# sound-detector.net
KiCad netlist of a schematic drawn in EAGLE
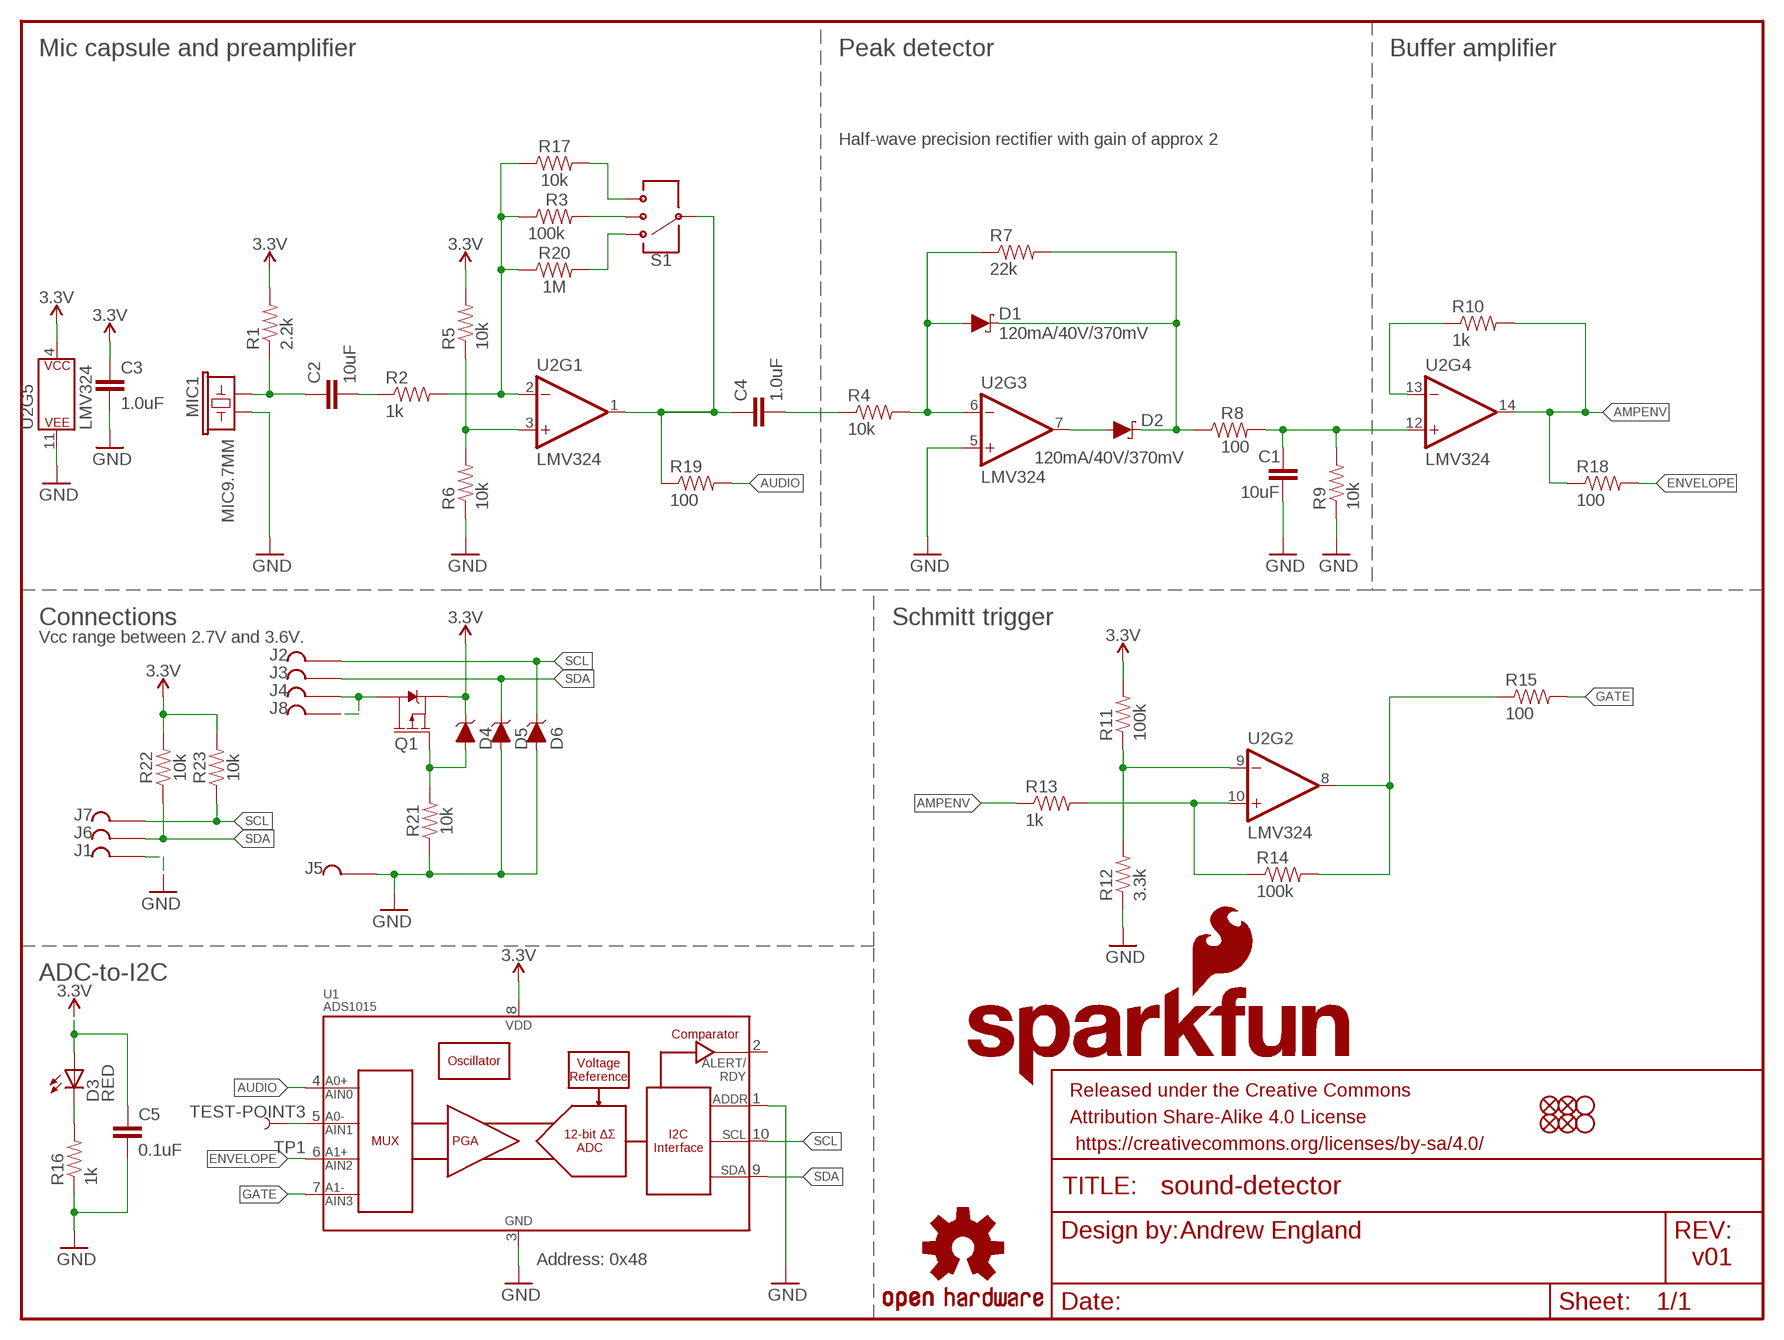
[diagram p0: schematic, sheet 1]

(export (version "E")
  (design (tool "Eeschema 10.0.6"))
  (components
    (comp (ref "C1")
      (value "10uF")
      (footprint "eagle-import:1206@1")
      (libsource (lib "eagle-import") (part "10UF-6.3V-20%(1206)"))
    )
    (comp (ref "C2")
      (value "10uF")
      (footprint "eagle-import:1206@1")
      (libsource (lib "eagle-import") (part "10UF-6.3V-20%(1206)"))
    )
    (comp (ref "C3")
      (value "1.0uF")
      (footprint "eagle-import:0603")
      (libsource (lib "eagle-import") (part "1.0UF-0603-16V-10%"))
    )
    (comp (ref "C4")
      (value "1.0uF")
      (footprint "eagle-import:0603")
      (libsource (lib "eagle-import") (part "1.0UF-0603-16V-10%"))
    )
    (comp (ref "C5")
      (value "0.1uF")
      (footprint "eagle-import:0603")
      (libsource (lib "eagle-import") (part "0.1UF-0603-25V-(+80/-20%)"))
    )
    (comp (ref "D1")
      (value "120mA/40V/370mV")
      (footprint "eagle-import:SOD-523")
      (libsource (lib "eagle-import") (part "DIODE-SCHOTTKY-RB751S40"))
    )
    (comp (ref "D2")
      (value "120mA/40V/370mV")
      (footprint "eagle-import:SOD-523")
      (libsource (lib "eagle-import") (part "DIODE-SCHOTTKY-RB751S40"))
    )
    (comp (ref "D3")
      (value "RED")
      (footprint "eagle-import:LED-0603")
      (libsource (lib "eagle-import") (part "LED-RED0603"))
    )
    (comp (ref "D4")
      (value "3.6V")
      (footprint "eagle-import:SOD-323")
      (libsource (lib "eagle-import") (part "DIODE-ZENER-BZT52C3V6S"))
    )
    (comp (ref "D5")
      (value "3.6V")
      (footprint "eagle-import:SOD-323")
      (libsource (lib "eagle-import") (part "DIODE-ZENER-BZT52C3V6S"))
    )
    (comp (ref "D6")
      (value "3.6V")
      (footprint "eagle-import:SOD-323")
      (libsource (lib "eagle-import") (part "DIODE-ZENER-BZT52C3V6S"))
    )
    (comp (ref "FID1")
      (value "FIDUCIAL1X2")
      (footprint "eagle-import:FIDUCIAL-1X2")
      (libsource (lib "eagle-import") (part "FIDUCIAL1X2"))
    )
    (comp (ref "FID2")
      (value "FIDUCIAL1X2")
      (footprint "eagle-import:FIDUCIAL-1X2")
      (libsource (lib "eagle-import") (part "FIDUCIAL1X2"))
    )
    (comp (ref "FID3")
      (value "FIDUCIAL1X2")
      (footprint "eagle-import:FIDUCIAL-1X2")
      (libsource (lib "eagle-import") (part "FIDUCIAL1X2"))
    )
    (comp (ref "FID4")
      (value "FIDUCIAL1X2")
      (footprint "eagle-import:FIDUCIAL-1X2")
      (libsource (lib "eagle-import") (part "FIDUCIAL1X2"))
    )
    (comp (ref "FRAME1")
      (value "FRAME-LETTER")
      (footprint "eagle-import:CREATIVE_COMMONS")
      (libsource (lib "eagle-import") (part "FRAME-LETTER"))
    )
    (comp (ref "H1")
      (value "STAND-OFFTIGHT")
      (footprint "eagle-import:STAND-OFF-TIGHT")
      (libsource (lib "eagle-import") (part "STAND-OFFTIGHT"))
    )
    (comp (ref "H2")
      (value "STAND-OFFTIGHT")
      (footprint "eagle-import:STAND-OFF-TIGHT")
      (libsource (lib "eagle-import") (part "STAND-OFFTIGHT"))
    )
    (comp (ref "J1")
      (value "GATORGATOR_MINI")
      (footprint "eagle-import:GATOR_MINI")
      (libsource (lib "eagle-import") (part "GATORGATOR_MINI"))
    )
    (comp (ref "J2")
      (value "GATORGATOR_MINI")
      (footprint "eagle-import:GATOR_MINI")
      (libsource (lib "eagle-import") (part "GATORGATOR_MINI"))
    )
    (comp (ref "J3")
      (value "GATORGATOR_MINI")
      (footprint "eagle-import:GATOR_MINI")
      (libsource (lib "eagle-import") (part "GATORGATOR_MINI"))
    )
    (comp (ref "J4")
      (value "GATORGATOR_MINI")
      (footprint "eagle-import:GATOR_MINI")
      (libsource (lib "eagle-import") (part "GATORGATOR_MINI"))
    )
    (comp (ref "J5")
      (value "GATORGATOR_MINI")
      (footprint "eagle-import:GATOR_MINI")
      (libsource (lib "eagle-import") (part "GATORGATOR_MINI"))
    )
    (comp (ref "J6")
      (value "GATORGATOR_MINI")
      (footprint "eagle-import:GATOR_MINI")
      (libsource (lib "eagle-import") (part "GATORGATOR_MINI"))
    )
    (comp (ref "J7")
      (value "GATORGATOR_MINI")
      (footprint "eagle-import:GATOR_MINI")
      (libsource (lib "eagle-import") (part "GATORGATOR_MINI"))
    )
    (comp (ref "J8")
      (value "GATORGATOR_MINI")
      (footprint "eagle-import:GATOR_MINI")
      (libsource (lib "eagle-import") (part "GATORGATOR_MINI"))
    )
    (comp (ref "LOGO1")
      (value "OSHW-LOGOS")
      (footprint "eagle-import:OSHW-LOGO-S")
      (libsource (lib "eagle-import") (part "OSHW-LOGOS"))
    )
    (comp (ref "LOGO2")
      (value "SFE_LOGO_NAME_FLAME.2_INCH")
      (footprint "eagle-import:SFE_LOGO_NAME_FLAME_.2")
      (libsource (lib "eagle-import") (part "SFE_LOGO_NAME_FLAME.2_INCH"))
    )
    (comp (ref "LOGO3")
      (value "SFE_LOGO_FLAME.2_INCH")
      (footprint "eagle-import:SFE_LOGO_FLAME_.2")
      (libsource (lib "eagle-import") (part "SFE_LOGO_FLAME.2_INCH"))
    )
    (comp (ref "MIC1")
      (value "MIC9.7MM")
      (footprint "eagle-import:MIC-9.7MM")
      (libsource (lib "eagle-import") (part "MIC9.7MM"))
    )
    (comp (ref "Q1")
      (value "2.5A/30V/105mΩ")
      (footprint "eagle-import:SOT23-3")
      (libsource (lib "eagle-import") (part "MOSFET_PCH-DMG2307L"))
    )
    (comp (ref "R1")
      (value "2.2k")
      (footprint "eagle-import:0603")
      (libsource (lib "eagle-import") (part "2.2KOHM-0603-1/10W-1%"))
    )
    (comp (ref "R2")
      (value "1k")
      (footprint "eagle-import:0603")
      (libsource (lib "eagle-import") (part "1KOHM-0603-1/10W-1%"))
    )
    (comp (ref "R3")
      (value "100k")
      (footprint "eagle-import:0603")
      (libsource (lib "eagle-import") (part "100KOHM-0603-1/10W-1%"))
    )
    (comp (ref "R4")
      (value "10k")
      (footprint "eagle-import:0603")
      (libsource (lib "eagle-import") (part "10KOHM-0603-1/10W-1%"))
    )
    (comp (ref "R5")
      (value "10k")
      (footprint "eagle-import:0603")
      (libsource (lib "eagle-import") (part "10KOHM-0603-1/10W-1%"))
    )
    (comp (ref "R6")
      (value "10k")
      (footprint "eagle-import:0603")
      (libsource (lib "eagle-import") (part "10KOHM-0603-1/10W-1%"))
    )
    (comp (ref "R7")
      (value "22k")
      (footprint "eagle-import:0603")
      (libsource (lib "eagle-import") (part "22KOHM-0603-1/10W-1%"))
    )
    (comp (ref "R8")
      (value "100")
      (footprint "eagle-import:0603")
      (libsource (lib "eagle-import") (part "100OHM-0603-1/10W-1%"))
    )
    (comp (ref "R9")
      (value "10k")
      (footprint "eagle-import:0603")
      (libsource (lib "eagle-import") (part "10KOHM-0603-1/10W-1%"))
    )
    (comp (ref "R10")
      (value "1k")
      (footprint "eagle-import:0603")
      (libsource (lib "eagle-import") (part "1KOHM-0603-1/10W-1%"))
    )
    (comp (ref "R11")
      (value "100k")
      (footprint "eagle-import:0603")
      (libsource (lib "eagle-import") (part "100KOHM-0603-1/10W-1%"))
    )
    (comp (ref "R12")
      (value "3.3k")
      (footprint "eagle-import:0603")
      (libsource (lib "eagle-import") (part "3.3KOHM-0603-1/10W-1%"))
    )
    (comp (ref "R13")
      (value "1k")
      (footprint "eagle-import:0603")
      (libsource (lib "eagle-import") (part "1KOHM-0603-1/10W-1%"))
    )
    (comp (ref "R14")
      (value "100k")
      (footprint "eagle-import:0603")
      (libsource (lib "eagle-import") (part "100KOHM-0603-1/10W-1%"))
    )
    (comp (ref "R15")
      (value "100")
      (footprint "eagle-import:0603")
      (libsource (lib "eagle-import") (part "100OHM-0603-1/10W-1%"))
    )
    (comp (ref "R16")
      (value "1k")
      (footprint "eagle-import:0603")
      (libsource (lib "eagle-import") (part "1KOHM-0603-1/10W-1%"))
    )
    (comp (ref "R17")
      (value "10k")
      (footprint "eagle-import:0603")
      (libsource (lib "eagle-import") (part "10KOHM-0603-1/10W-1%"))
    )
    (comp (ref "R18")
      (value "100")
      (footprint "eagle-import:0603")
      (libsource (lib "eagle-import") (part "100OHM-0603-1/10W-1%"))
    )
    (comp (ref "R19")
      (value "100")
      (footprint "eagle-import:0603")
      (libsource (lib "eagle-import") (part "100OHM-0603-1/10W-1%"))
    )
    (comp (ref "R20")
      (value "1M")
      (footprint "eagle-import:0603")
      (libsource (lib "eagle-import") (part "1MOHM-0603-1/4W-5%"))
    )
    (comp (ref "R21")
      (value "10k")
      (footprint "eagle-import:0603")
      (libsource (lib "eagle-import") (part "10KOHM-0603-1/10W-1%"))
    )
    (comp (ref "R22")
      (value "10k")
      (footprint "eagle-import:0603")
      (libsource (lib "eagle-import") (part "10KOHM-0603-1/10W-1%"))
    )
    (comp (ref "R23")
      (value "10k")
      (footprint "eagle-import:0603")
      (libsource (lib "eagle-import") (part "10KOHM-0603-1/10W-1%"))
    )
    (comp (ref "S1")
      (value "SWITCH-SP3T-SMD")
      (footprint "eagle-import:SWITCH_SP3T_SMD")
      (libsource (lib "eagle-import") (part "SWITCH-SP3T-SMD"))
    )
    (comp (ref "TP1")
      (value "TEST-POINT3")
      (footprint "eagle-import:PAD.03X.03")
      (libsource (lib "eagle-import") (part "TEST-POINT3"))
    )
    (comp (ref "U1")
      (value "ADS1015")
      (footprint "eagle-import:MSOP10")
      (libsource (lib "eagle-import") (part "ADS1015"))
    )
    (comp (ref "U2")
      (value "LMV324")
      (footprint "eagle-import:SO14")
      (libsource (lib "eagle-import") (part "LMV324"))
    )
  )
  (nets
    (net (code "1") (name "3.3V") (class "Default")
      (node (ref "C3") (pin "1") (pinfunction "1_1") (pintype "passive"))
      (node (ref "C5") (pin "1") (pinfunction "1_1") (pintype "passive"))
      (node (ref "D3") (pin "A") (pinfunction "A_A") (pintype "passive"))
      (node (ref "D4") (pin "C") (pinfunction "C_C") (pintype "passive"))
      (node (ref "Q1") (pin "2") (pinfunction "S_2") (pintype "bidirectional"))
      (node (ref "R1") (pin "2") (pinfunction "2_2") (pintype "passive"))
      (node (ref "R11") (pin "2") (pinfunction "2_2") (pintype "passive"))
      (node (ref "R22") (pin "2") (pinfunction "2_2") (pintype "passive"))
      (node (ref "R23") (pin "2") (pinfunction "2_2") (pintype "passive"))
      (node (ref "R5") (pin "2") (pinfunction "2_2") (pintype "passive"))
      (node (ref "U1") (pin "8") (pinfunction "VDD_8") (pintype "bidirectional"))
      (node (ref "U2") (pin "4") (pinfunction "P$V+_4") (pintype "bidirectional"))
    )
    (net (code "2") (name "AMPENV") (class "Default")
      (node (ref "R10") (pin "2") (pinfunction "2_2") (pintype "passive"))
      (node (ref "R13") (pin "1") (pinfunction "1_1") (pintype "passive"))
      (node (ref "R18") (pin "1") (pinfunction "1_1") (pintype "passive"))
      (node (ref "U2") (pin "14") (pinfunction "OUT_14") (pintype "output"))
    )
    (net (code "3") (name "AUDIO") (class "Default")
      (node (ref "R19") (pin "2") (pinfunction "2_2") (pintype "passive"))
      (node (ref "U1") (pin "4") (pinfunction "AIN0_4") (pintype "bidirectional"))
    )
    (net (code "4") (name "ENVELOPE") (class "Default")
      (node (ref "R18") (pin "2") (pinfunction "2_2") (pintype "passive"))
      (node (ref "U1") (pin "6") (pinfunction "AIN2_6") (pintype "bidirectional"))
    )
    (net (code "5") (name "GATE") (class "Default")
      (node (ref "R15") (pin "2") (pinfunction "2_2") (pintype "passive"))
      (node (ref "U1") (pin "7") (pinfunction "AIN3_7") (pintype "bidirectional"))
    )
    (net (code "6") (name "GND") (class "Default")
      (node (ref "C1") (pin "2") (pinfunction "2_2") (pintype "passive"))
      (node (ref "C3") (pin "2") (pinfunction "2_2") (pintype "passive"))
      (node (ref "C5") (pin "2") (pinfunction "2_2") (pintype "passive"))
      (node (ref "D5") (pin "A") (pinfunction "A_A") (pintype "passive"))
      (node (ref "D6") (pin "A") (pinfunction "A_A") (pintype "passive"))
      (node (ref "J1") (pin "P$2") (pinfunction "P$1_P$2") (pintype "bidirectional"))
      (node (ref "J5") (pin "P$2") (pinfunction "P$1_P$2") (pintype "bidirectional"))
      (node (ref "MIC1") (pin "2") (pinfunction "2_2") (pintype "passive"))
      (node (ref "R12") (pin "1") (pinfunction "1_1") (pintype "passive"))
      (node (ref "R16") (pin "1") (pinfunction "1_1") (pintype "passive"))
      (node (ref "R21") (pin "1") (pinfunction "1_1") (pintype "passive"))
      (node (ref "R6") (pin "1") (pinfunction "1_1") (pintype "passive"))
      (node (ref "R9") (pin "1") (pinfunction "1_1") (pintype "passive"))
      (node (ref "U1") (pin "1") (pinfunction "ADDR_1") (pintype "bidirectional"))
      (node (ref "U1") (pin "3") (pinfunction "VSS_3") (pintype "bidirectional"))
      (node (ref "U2") (pin "11") (pinfunction "P$V-_11") (pintype "bidirectional"))
      (node (ref "U2") (pin "5") (pinfunction "+IN_5") (pintype "input"))
    )
    (net (code "7") (name "Net-(C2-Pad1)") (class "Default")
      (node (ref "C2") (pin "1") (pinfunction "1_1") (pintype "passive"))
      (node (ref "MIC1") (pin "1") (pinfunction "1_1") (pintype "passive"))
      (node (ref "R1") (pin "1") (pinfunction "1_1") (pintype "passive"))
    )
    (net (code "8") (name "Net-(C2-Pad2)") (class "Default")
      (node (ref "C2") (pin "2") (pinfunction "2_2") (pintype "passive"))
      (node (ref "R2") (pin "1") (pinfunction "1_1") (pintype "passive"))
    )
    (net (code "9") (name "Net-(C4-Pad2)") (class "Default")
      (node (ref "C4") (pin "2") (pinfunction "2_2") (pintype "passive"))
      (node (ref "R4") (pin "1") (pinfunction "1_1") (pintype "passive"))
    )
    (net (code "10") (name "Net-(D1-PadC)") (class "Default")
      (node (ref "D1") (pin "C") (pinfunction "C_C") (pintype "passive"))
      (node (ref "D2") (pin "C") (pinfunction "C_C") (pintype "passive"))
      (node (ref "R7") (pin "2") (pinfunction "2_2") (pintype "passive"))
      (node (ref "R8") (pin "1") (pinfunction "1_1") (pintype "passive"))
    )
    (net (code "11") (name "Net-(D3-PadC)") (class "Default")
      (node (ref "D3") (pin "C") (pinfunction "C_C") (pintype "passive"))
      (node (ref "R16") (pin "2") (pinfunction "2_2") (pintype "passive"))
    )
    (net (code "12") (name "Net-(J4-P$1)") (class "Default")
      (node (ref "J4") (pin "P$2") (pinfunction "P$1_P$2") (pintype "bidirectional"))
      (node (ref "J8") (pin "P$2") (pinfunction "P$1_P$2") (pintype "bidirectional"))
      (node (ref "Q1") (pin "3") (pinfunction "D_3") (pintype "bidirectional"))
    )
    (net (code "13") (name "Net-(Q1-G)") (class "Default")
      (node (ref "D4") (pin "A") (pinfunction "A_A") (pintype "passive"))
      (node (ref "Q1") (pin "1") (pinfunction "G_1") (pintype "bidirectional"))
      (node (ref "R21") (pin "2") (pinfunction "2_2") (pintype "passive"))
    )
    (net (code "14") (name "Net-(R3-Pad2)") (class "Default")
      (node (ref "R3") (pin "2") (pinfunction "2_2") (pintype "passive"))
      (node (ref "S1") (pin "2") (pinfunction "2_2") (pintype "bidirectional"))
    )
    (net (code "15") (name "Net-(R17-Pad2)") (class "Default")
      (node (ref "R17") (pin "2") (pinfunction "2_2") (pintype "passive"))
      (node (ref "S1") (pin "4") (pinfunction "4_4") (pintype "bidirectional"))
    )
    (net (code "16") (name "Net-(R20-Pad2)") (class "Default")
      (node (ref "R20") (pin "2") (pinfunction "2_2") (pintype "passive"))
      (node (ref "S1") (pin "1") (pinfunction "1_1") (pintype "bidirectional"))
    )
    (net (code "17") (name "Net-(TP1-1)") (class "Default")
      (node (ref "TP1") (pin "P$1") (pinfunction "1_P$1") (pintype "bidirectional"))
      (node (ref "U1") (pin "5") (pinfunction "AIN1_5") (pintype "bidirectional"))
    )
    (net (code "18") (name "Net-(U2A-+IN)") (class "Default")
      (node (ref "R5") (pin "1") (pinfunction "1_1") (pintype "passive"))
      (node (ref "R6") (pin "2") (pinfunction "2_2") (pintype "passive"))
      (node (ref "U2") (pin "3") (pinfunction "+IN_3") (pintype "input"))
    )
    (net (code "19") (name "Net-(U2A--IN)") (class "Default")
      (node (ref "R17") (pin "1") (pinfunction "1_1") (pintype "passive"))
      (node (ref "R2") (pin "2") (pinfunction "2_2") (pintype "passive"))
      (node (ref "R20") (pin "1") (pinfunction "1_1") (pintype "passive"))
      (node (ref "R3") (pin "1") (pinfunction "1_1") (pintype "passive"))
      (node (ref "U2") (pin "2") (pinfunction "-IN_2") (pintype "input"))
    )
    (net (code "20") (name "Net-(U2A-OUT)") (class "Default")
      (node (ref "C4") (pin "1") (pinfunction "1_1") (pintype "passive"))
      (node (ref "R19") (pin "1") (pinfunction "1_1") (pintype "passive"))
      (node (ref "S1") (pin "3") (pinfunction "3_3") (pintype "bidirectional"))
      (node (ref "U2") (pin "1") (pinfunction "OUT_1") (pintype "output"))
    )
    (net (code "21") (name "Net-(U2B-+IN)") (class "Default")
      (node (ref "R13") (pin "2") (pinfunction "2_2") (pintype "passive"))
      (node (ref "R14") (pin "1") (pinfunction "1_1") (pintype "passive"))
      (node (ref "U2") (pin "10") (pinfunction "+IN_10") (pintype "input"))
    )
    (net (code "22") (name "Net-(U2B--IN)") (class "Default")
      (node (ref "R11") (pin "1") (pinfunction "1_1") (pintype "passive"))
      (node (ref "R12") (pin "2") (pinfunction "2_2") (pintype "passive"))
      (node (ref "U2") (pin "9") (pinfunction "-IN_9") (pintype "input"))
    )
    (net (code "23") (name "Net-(U2B-OUT)") (class "Default")
      (node (ref "R14") (pin "2") (pinfunction "2_2") (pintype "passive"))
      (node (ref "R15") (pin "1") (pinfunction "1_1") (pintype "passive"))
      (node (ref "U2") (pin "8") (pinfunction "OUT_8") (pintype "output"))
    )
    (net (code "24") (name "Net-(U2C--IN)") (class "Default")
      (node (ref "D1") (pin "A") (pinfunction "A_A") (pintype "passive"))
      (node (ref "R4") (pin "2") (pinfunction "2_2") (pintype "passive"))
      (node (ref "R7") (pin "1") (pinfunction "1_1") (pintype "passive"))
      (node (ref "U2") (pin "6") (pinfunction "-IN_6") (pintype "input"))
    )
    (net (code "25") (name "Net-(U2C-OUT)") (class "Default")
      (node (ref "D2") (pin "A") (pinfunction "A_A") (pintype "passive"))
      (node (ref "U2") (pin "7") (pinfunction "OUT_7") (pintype "output"))
    )
    (net (code "26") (name "Net-(U2D-+IN)") (class "Default")
      (node (ref "C1") (pin "1") (pinfunction "1_1") (pintype "passive"))
      (node (ref "R8") (pin "2") (pinfunction "2_2") (pintype "passive"))
      (node (ref "R9") (pin "2") (pinfunction "2_2") (pintype "passive"))
      (node (ref "U2") (pin "12") (pinfunction "+IN_12") (pintype "input"))
    )
    (net (code "27") (name "Net-(U2D--IN)") (class "Default")
      (node (ref "R10") (pin "1") (pinfunction "1_1") (pintype "passive"))
      (node (ref "U2") (pin "13") (pinfunction "-IN_13") (pintype "input"))
    )
    (net (code "28") (name "SCL") (class "Default")
      (node (ref "D6") (pin "C") (pinfunction "C_C") (pintype "passive"))
      (node (ref "J2") (pin "P$2") (pinfunction "P$1_P$2") (pintype "bidirectional"))
      (node (ref "J7") (pin "P$2") (pinfunction "P$1_P$2") (pintype "bidirectional"))
      (node (ref "R23") (pin "1") (pinfunction "1_1") (pintype "passive"))
      (node (ref "U1") (pin "10") (pinfunction "SCL_10") (pintype "bidirectional"))
    )
    (net (code "29") (name "SDA") (class "Default")
      (node (ref "D5") (pin "C") (pinfunction "C_C") (pintype "passive"))
      (node (ref "J3") (pin "P$2") (pinfunction "P$1_P$2") (pintype "bidirectional"))
      (node (ref "J6") (pin "P$2") (pinfunction "P$1_P$2") (pintype "bidirectional"))
      (node (ref "R22") (pin "1") (pinfunction "1_1") (pintype "passive"))
      (node (ref "U1") (pin "9") (pinfunction "SDA_9") (pintype "bidirectional"))
    )
    (net (code "30") (name "unconnected-(U1-ALERT{slash}RDY-Pad2)") (class "Default")
      (node (ref "U1") (pin "2") (pinfunction "ALERT/RDY_2") (pintype "bidirectional"))
    )
  )
)
